# AD7799.net
KiCad netlist of a schematic drawn in Altium Designer
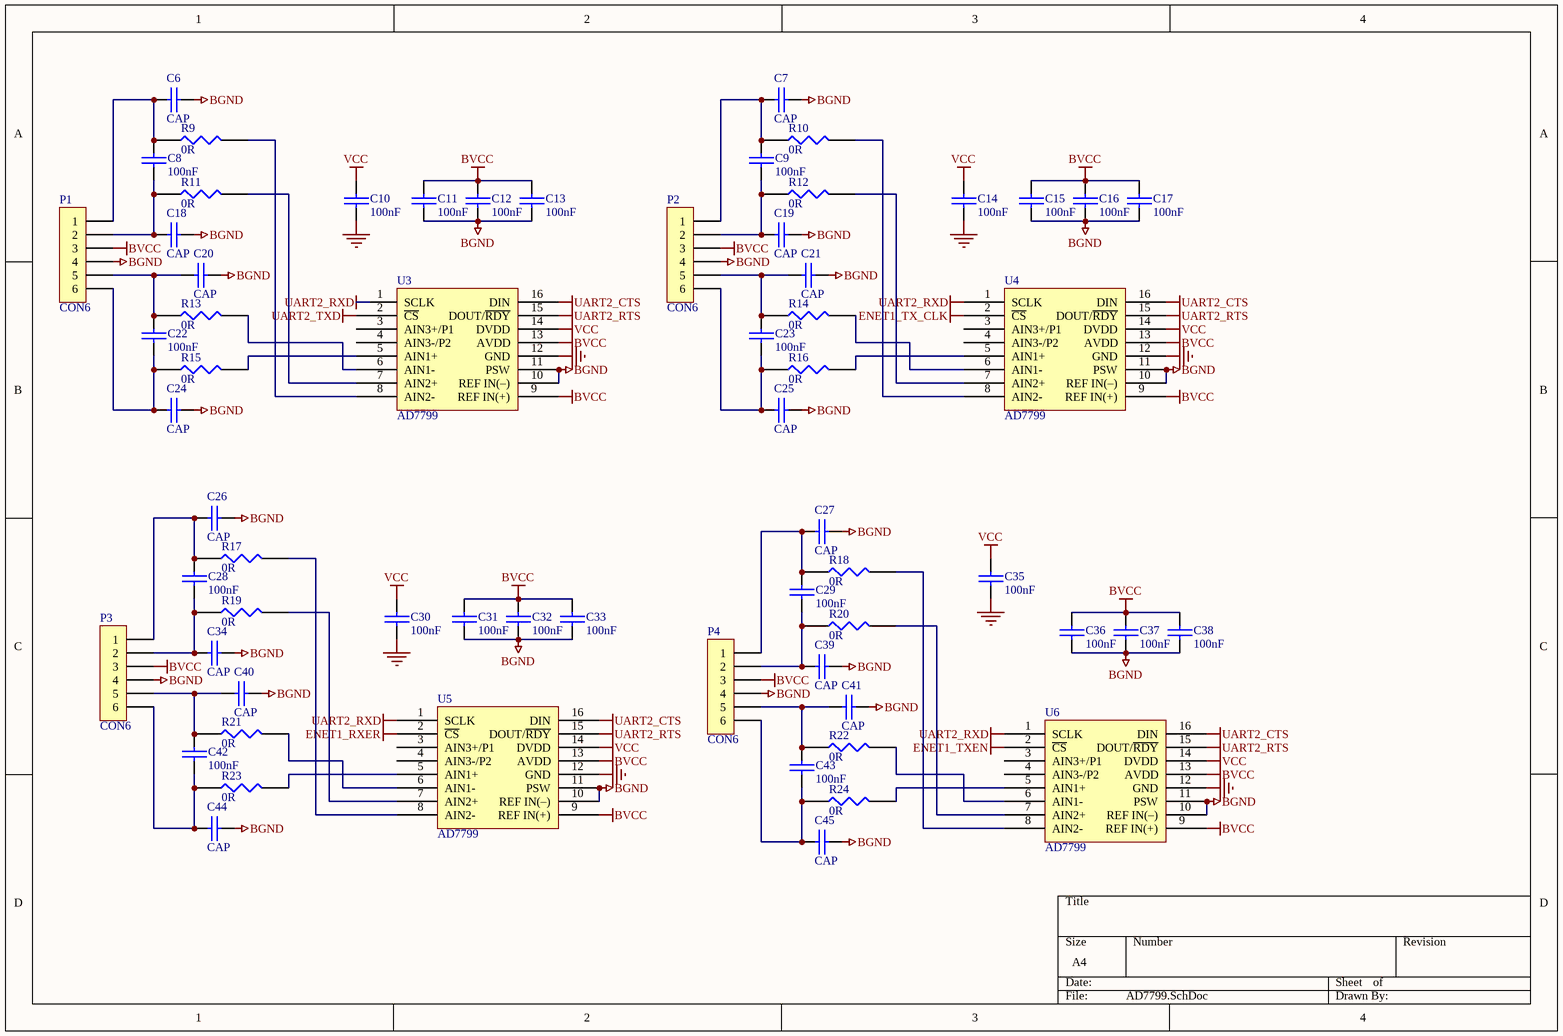
[diagram p0: AD7799.SchDoc]

(export (version "E")
  (design (tool "Eeschema 10.0.6"))
  (components
    (comp (ref "C6")
      (value "CAP")
      (footprint "0603_C")
      (description "Capacitor")
      (libsource (lib "*") (part "CAP"))
    )
    (comp (ref "C7")
      (value "CAP")
      (footprint "0603_C")
      (description "Capacitor")
      (libsource (lib "*") (part "CAP"))
    )
    (comp (ref "C8")
      (value "100nF")
      (footprint "0603_C")
      (description "Capacitor")
      (libsource (lib "*") (part "CAP"))
    )
    (comp (ref "C9")
      (value "100nF")
      (footprint "0603_C")
      (description "Capacitor")
      (libsource (lib "*") (part "CAP"))
    )
    (comp (ref "C10")
      (value "100nF")
      (footprint "0603_C")
      (description "Capacitor")
      (libsource (lib "*") (part "CAP"))
    )
    (comp (ref "C11")
      (value "100nF")
      (footprint "0603_C")
      (description "Capacitor")
      (libsource (lib "*") (part "CAP"))
    )
    (comp (ref "C12")
      (value "100nF")
      (footprint "0603_C")
      (description "Capacitor")
      (libsource (lib "*") (part "CAP"))
    )
    (comp (ref "C13")
      (value "100nF")
      (footprint "0603_C")
      (description "Capacitor")
      (libsource (lib "*") (part "CAP"))
    )
    (comp (ref "C14")
      (value "100nF")
      (footprint "0603_C")
      (description "Capacitor")
      (libsource (lib "*") (part "CAP"))
    )
    (comp (ref "C15")
      (value "100nF")
      (footprint "0603_C")
      (description "Capacitor")
      (libsource (lib "*") (part "CAP"))
    )
    (comp (ref "C16")
      (value "100nF")
      (footprint "0603_C")
      (description "Capacitor")
      (libsource (lib "*") (part "CAP"))
    )
    (comp (ref "C17")
      (value "100nF")
      (footprint "0603_C")
      (description "Capacitor")
      (libsource (lib "*") (part "CAP"))
    )
    (comp (ref "C18")
      (value "CAP")
      (footprint "0603_C")
      (description "Capacitor")
      (libsource (lib "*") (part "CAP"))
    )
    (comp (ref "C19")
      (value "CAP")
      (footprint "0603_C")
      (description "Capacitor")
      (libsource (lib "*") (part "CAP"))
    )
    (comp (ref "C20")
      (value "CAP")
      (footprint "0603_C")
      (description "Capacitor")
      (libsource (lib "*") (part "CAP"))
    )
    (comp (ref "C21")
      (value "CAP")
      (footprint "0603_C")
      (description "Capacitor")
      (libsource (lib "*") (part "CAP"))
    )
    (comp (ref "C22")
      (value "100nF")
      (footprint "0603_C")
      (description "Capacitor")
      (libsource (lib "*") (part "CAP"))
    )
    (comp (ref "C23")
      (value "100nF")
      (footprint "0603_C")
      (description "Capacitor")
      (libsource (lib "*") (part "CAP"))
    )
    (comp (ref "C24")
      (value "CAP")
      (footprint "0603_C")
      (description "Capacitor")
      (libsource (lib "*") (part "CAP"))
    )
    (comp (ref "C25")
      (value "CAP")
      (footprint "0603_C")
      (description "Capacitor")
      (libsource (lib "*") (part "CAP"))
    )
    (comp (ref "C26")
      (value "CAP")
      (footprint "0603_C")
      (description "Capacitor")
      (libsource (lib "*") (part "CAP"))
    )
    (comp (ref "C27")
      (value "CAP")
      (footprint "0603_C")
      (description "Capacitor")
      (libsource (lib "*") (part "CAP"))
    )
    (comp (ref "C28")
      (value "100nF")
      (footprint "0603_C")
      (description "Capacitor")
      (libsource (lib "*") (part "CAP"))
    )
    (comp (ref "C29")
      (value "100nF")
      (footprint "0603_C")
      (description "Capacitor")
      (libsource (lib "*") (part "CAP"))
    )
    (comp (ref "C30")
      (value "100nF")
      (footprint "0603_C")
      (description "Capacitor")
      (libsource (lib "*") (part "CAP"))
    )
    (comp (ref "C31")
      (value "100nF")
      (footprint "0603_C")
      (description "Capacitor")
      (libsource (lib "*") (part "CAP"))
    )
    (comp (ref "C32")
      (value "100nF")
      (footprint "0603_C")
      (description "Capacitor")
      (libsource (lib "*") (part "CAP"))
    )
    (comp (ref "C33")
      (value "100nF")
      (footprint "0603_C")
      (description "Capacitor")
      (libsource (lib "*") (part "CAP"))
    )
    (comp (ref "C34")
      (value "CAP")
      (footprint "0603_C")
      (description "Capacitor")
      (libsource (lib "*") (part "CAP"))
    )
    (comp (ref "C35")
      (value "100nF")
      (footprint "0603_C")
      (description "Capacitor")
      (libsource (lib "*") (part "CAP"))
    )
    (comp (ref "C36")
      (value "100nF")
      (footprint "0603_C")
      (description "Capacitor")
      (libsource (lib "*") (part "CAP"))
    )
    (comp (ref "C37")
      (value "100nF")
      (footprint "0603_C")
      (description "Capacitor")
      (libsource (lib "*") (part "CAP"))
    )
    (comp (ref "C38")
      (value "100nF")
      (footprint "0603_C")
      (description "Capacitor")
      (libsource (lib "*") (part "CAP"))
    )
    (comp (ref "C39")
      (value "CAP")
      (footprint "0603_C")
      (description "Capacitor")
      (libsource (lib "*") (part "CAP"))
    )
    (comp (ref "C40")
      (value "CAP")
      (footprint "0603_C")
      (description "Capacitor")
      (libsource (lib "*") (part "CAP"))
    )
    (comp (ref "C41")
      (value "CAP")
      (footprint "0603_C")
      (description "Capacitor")
      (libsource (lib "*") (part "CAP"))
    )
    (comp (ref "C42")
      (value "100nF")
      (footprint "0603_C")
      (description "Capacitor")
      (libsource (lib "*") (part "CAP"))
    )
    (comp (ref "C43")
      (value "100nF")
      (footprint "0603_C")
      (description "Capacitor")
      (libsource (lib "*") (part "CAP"))
    )
    (comp (ref "C44")
      (value "CAP")
      (footprint "0603_C")
      (description "Capacitor")
      (libsource (lib "*") (part "CAP"))
    )
    (comp (ref "C45")
      (value "CAP")
      (footprint "0603_C")
      (description "Capacitor")
      (libsource (lib "*") (part "CAP"))
    )
    (comp (ref "P1")
      (value "CON6")
      (footprint "DB142V-5.08-6P")
      (description "Connector")
      (libsource (lib "*") (part "CON6"))
    )
    (comp (ref "P2")
      (value "CON6")
      (footprint "DB142V-5.08-6P")
      (description "Connector")
      (libsource (lib "*") (part "CON6"))
    )
    (comp (ref "P3")
      (value "CON6")
      (footprint "DB142V-5.08-6P")
      (description "Connector")
      (libsource (lib "*") (part "CON6"))
    )
    (comp (ref "P4")
      (value "CON6")
      (footprint "DB142V-5.08-6P")
      (description "Connector")
      (libsource (lib "*") (part "CON6"))
    )
    (comp (ref "R9") (value "0R") (footprint "0603_R") (libsource (lib "*") (part "RES1")))
    (comp (ref "R10") (value "0R") (footprint "0603_R") (libsource (lib "*") (part "RES1")))
    (comp (ref "R11") (value "0R") (footprint "0603_R") (libsource (lib "*") (part "RES1")))
    (comp (ref "R12") (value "0R") (footprint "0603_R") (libsource (lib "*") (part "RES1")))
    (comp (ref "R13") (value "0R") (footprint "0603_R") (libsource (lib "*") (part "RES1")))
    (comp (ref "R14") (value "0R") (footprint "0603_R") (libsource (lib "*") (part "RES1")))
    (comp (ref "R15") (value "0R") (footprint "0603_R") (libsource (lib "*") (part "RES1")))
    (comp (ref "R16") (value "0R") (footprint "0603_R") (libsource (lib "*") (part "RES1")))
    (comp (ref "R17") (value "0R") (footprint "0603_R") (libsource (lib "*") (part "RES1")))
    (comp (ref "R18") (value "0R") (footprint "0603_R") (libsource (lib "*") (part "RES1")))
    (comp (ref "R19") (value "0R") (footprint "0603_R") (libsource (lib "*") (part "RES1")))
    (comp (ref "R20") (value "0R") (footprint "0603_R") (libsource (lib "*") (part "RES1")))
    (comp (ref "R21") (value "0R") (footprint "0603_R") (libsource (lib "*") (part "RES1")))
    (comp (ref "R22") (value "0R") (footprint "0603_R") (libsource (lib "*") (part "RES1")))
    (comp (ref "R23") (value "0R") (footprint "0603_R") (libsource (lib "*") (part "RES1")))
    (comp (ref "R24") (value "0R") (footprint "0603_R") (libsource (lib "*") (part "RES1")))
    (comp (ref "U3") (value "AD7799") (footprint "TSSOP16") (libsource (lib "*") (part "AD7799")))
    (comp (ref "U4") (value "AD7799") (footprint "TSSOP16") (libsource (lib "*") (part "AD7799")))
    (comp (ref "U5") (value "AD7799") (footprint "TSSOP16") (libsource (lib "*") (part "AD7799")))
    (comp (ref "U6") (value "AD7799") (footprint "TSSOP16") (libsource (lib "*") (part "AD7799")))
  )
  (nets
    (net (code "1") (name "BGND") (class "Default")
      (node (ref "C11") (pin "2") (pinfunction "2_2") (pintype "passive"))
      (node (ref "C12") (pin "2") (pinfunction "2_2") (pintype "passive"))
      (node (ref "C13") (pin "2") (pinfunction "2_2") (pintype "passive"))
      (node (ref "C15") (pin "2") (pinfunction "2_2") (pintype "passive"))
      (node (ref "C16") (pin "2") (pinfunction "2_2") (pintype "passive"))
      (node (ref "C17") (pin "2") (pinfunction "2_2") (pintype "passive"))
      (node (ref "C18") (pin "2") (pinfunction "2_2") (pintype "passive"))
      (node (ref "C19") (pin "2") (pinfunction "2_2") (pintype "passive"))
      (node (ref "C20") (pin "2") (pinfunction "2_2") (pintype "passive"))
      (node (ref "C21") (pin "2") (pinfunction "2_2") (pintype "passive"))
      (node (ref "C24") (pin "2") (pinfunction "2_2") (pintype "passive"))
      (node (ref "C25") (pin "2") (pinfunction "2_2") (pintype "passive"))
      (node (ref "C26") (pin "2") (pinfunction "2_2") (pintype "passive"))
      (node (ref "C27") (pin "2") (pinfunction "2_2") (pintype "passive"))
      (node (ref "C31") (pin "2") (pinfunction "2_2") (pintype "passive"))
      (node (ref "C32") (pin "2") (pinfunction "2_2") (pintype "passive"))
      (node (ref "C33") (pin "2") (pinfunction "2_2") (pintype "passive"))
      (node (ref "C34") (pin "2") (pinfunction "2_2") (pintype "passive"))
      (node (ref "C36") (pin "2") (pinfunction "2_2") (pintype "passive"))
      (node (ref "C37") (pin "2") (pinfunction "2_2") (pintype "passive"))
      (node (ref "C38") (pin "2") (pinfunction "2_2") (pintype "passive"))
      (node (ref "C39") (pin "2") (pinfunction "2_2") (pintype "passive"))
      (node (ref "C40") (pin "2") (pinfunction "2_2") (pintype "passive"))
      (node (ref "C41") (pin "2") (pinfunction "2_2") (pintype "passive"))
      (node (ref "C44") (pin "2") (pinfunction "2_2") (pintype "passive"))
      (node (ref "C45") (pin "2") (pinfunction "2_2") (pintype "passive"))
      (node (ref "C6") (pin "2") (pinfunction "2_2") (pintype "passive"))
      (node (ref "C7") (pin "2") (pinfunction "2_2") (pintype "passive"))
      (node (ref "P1") (pin "4") (pinfunction "4_4") (pintype "passive"))
      (node (ref "P2") (pin "4") (pinfunction "4_4") (pintype "passive"))
      (node (ref "P3") (pin "4") (pinfunction "4_4") (pintype "passive"))
      (node (ref "P4") (pin "4") (pinfunction "4_4") (pintype "passive"))
      (node (ref "U3") (pin "10") (pinfunction "REF_IN(–)_10") (pintype "passive"))
      (node (ref "U3") (pin "11") (pinfunction "PSW_11") (pintype "passive"))
      (node (ref "U4") (pin "10") (pinfunction "REF_IN(–)_10") (pintype "passive"))
      (node (ref "U4") (pin "11") (pinfunction "PSW_11") (pintype "passive"))
      (node (ref "U5") (pin "10") (pinfunction "REF_IN(–)_10") (pintype "passive"))
      (node (ref "U5") (pin "11") (pinfunction "PSW_11") (pintype "passive"))
      (node (ref "U6") (pin "10") (pinfunction "REF_IN(–)_10") (pintype "passive"))
      (node (ref "U6") (pin "11") (pinfunction "PSW_11") (pintype "passive"))
    )
    (net (code "2") (name "BVCC") (class "Default")
      (node (ref "C11") (pin "1") (pinfunction "1_1") (pintype "passive"))
      (node (ref "C12") (pin "1") (pinfunction "1_1") (pintype "passive"))
      (node (ref "C13") (pin "1") (pinfunction "1_1") (pintype "passive"))
      (node (ref "C15") (pin "1") (pinfunction "1_1") (pintype "passive"))
      (node (ref "C16") (pin "1") (pinfunction "1_1") (pintype "passive"))
      (node (ref "C17") (pin "1") (pinfunction "1_1") (pintype "passive"))
      (node (ref "C31") (pin "1") (pinfunction "1_1") (pintype "passive"))
      (node (ref "C32") (pin "1") (pinfunction "1_1") (pintype "passive"))
      (node (ref "C33") (pin "1") (pinfunction "1_1") (pintype "passive"))
      (node (ref "C36") (pin "1") (pinfunction "1_1") (pintype "passive"))
      (node (ref "C37") (pin "1") (pinfunction "1_1") (pintype "passive"))
      (node (ref "C38") (pin "1") (pinfunction "1_1") (pintype "passive"))
      (node (ref "P1") (pin "3") (pinfunction "3_3") (pintype "passive"))
      (node (ref "P2") (pin "3") (pinfunction "3_3") (pintype "passive"))
      (node (ref "P3") (pin "3") (pinfunction "3_3") (pintype "passive"))
      (node (ref "P4") (pin "3") (pinfunction "3_3") (pintype "passive"))
      (node (ref "U3") (pin "13") (pinfunction "AVDD_13") (pintype "passive"))
      (node (ref "U3") (pin "9") (pinfunction "REF_IN(+)_9") (pintype "passive"))
      (node (ref "U4") (pin "13") (pinfunction "AVDD_13") (pintype "passive"))
      (node (ref "U4") (pin "9") (pinfunction "REF_IN(+)_9") (pintype "passive"))
      (node (ref "U5") (pin "13") (pinfunction "AVDD_13") (pintype "passive"))
      (node (ref "U5") (pin "9") (pinfunction "REF_IN(+)_9") (pintype "passive"))
      (node (ref "U6") (pin "13") (pinfunction "AVDD_13") (pintype "passive"))
      (node (ref "U6") (pin "9") (pinfunction "REF_IN(+)_9") (pintype "passive"))
    )
    (net (code "3") (name "ENET1_RXER") (class "Default")
      (node (ref "U5") (pin "2") (pinfunction "~{CS}_2") (pintype "passive"))
    )
    (net (code "4") (name "ENET1_TXEN") (class "Default")
      (node (ref "U6") (pin "2") (pinfunction "~{CS}_2") (pintype "passive"))
    )
    (net (code "5") (name "ENET1_TX_CLK") (class "Default")
      (node (ref "U4") (pin "2") (pinfunction "~{CS}_2") (pintype "passive"))
    )
    (net (code "6") (name "GND") (class "Default")
      (node (ref "C10") (pin "2") (pinfunction "2_2") (pintype "passive"))
      (node (ref "C14") (pin "2") (pinfunction "2_2") (pintype "passive"))
      (node (ref "C30") (pin "2") (pinfunction "2_2") (pintype "passive"))
      (node (ref "C35") (pin "2") (pinfunction "2_2") (pintype "passive"))
      (node (ref "U3") (pin "12") (pinfunction "GND_12") (pintype "passive"))
      (node (ref "U4") (pin "12") (pinfunction "GND_12") (pintype "passive"))
      (node (ref "U5") (pin "12") (pinfunction "GND_12") (pintype "passive"))
      (node (ref "U6") (pin "12") (pinfunction "GND_12") (pintype "passive"))
    )
    (net (code "7") (name "Net-(C6-Pad1)") (class "Default")
      (node (ref "C6") (pin "1") (pinfunction "1_1") (pintype "passive"))
      (node (ref "C8") (pin "1") (pinfunction "1_1") (pintype "passive"))
      (node (ref "P1") (pin "1") (pinfunction "1_1") (pintype "passive"))
      (node (ref "R9") (pin "1") (pinfunction "1_1") (pintype "passive"))
    )
    (net (code "8") (name "Net-(C7-Pad1)") (class "Default")
      (node (ref "C7") (pin "1") (pinfunction "1_1") (pintype "passive"))
      (node (ref "C9") (pin "1") (pinfunction "1_1") (pintype "passive"))
      (node (ref "P2") (pin "1") (pinfunction "1_1") (pintype "passive"))
      (node (ref "R10") (pin "1") (pinfunction "1_1") (pintype "passive"))
    )
    (net (code "9") (name "Net-(C18-Pad1)") (class "Default")
      (node (ref "C18") (pin "1") (pinfunction "1_1") (pintype "passive"))
      (node (ref "C8") (pin "2") (pinfunction "2_2") (pintype "passive"))
      (node (ref "P1") (pin "2") (pinfunction "2_2") (pintype "passive"))
      (node (ref "R11") (pin "1") (pinfunction "1_1") (pintype "passive"))
    )
    (net (code "10") (name "Net-(C19-Pad1)") (class "Default")
      (node (ref "C19") (pin "1") (pinfunction "1_1") (pintype "passive"))
      (node (ref "C9") (pin "2") (pinfunction "2_2") (pintype "passive"))
      (node (ref "P2") (pin "2") (pinfunction "2_2") (pintype "passive"))
      (node (ref "R12") (pin "1") (pinfunction "1_1") (pintype "passive"))
    )
    (net (code "11") (name "Net-(C20-Pad1)") (class "Default")
      (node (ref "C20") (pin "1") (pinfunction "1_1") (pintype "passive"))
      (node (ref "C22") (pin "1") (pinfunction "1_1") (pintype "passive"))
      (node (ref "P1") (pin "5") (pinfunction "5_5") (pintype "passive"))
      (node (ref "R13") (pin "1") (pinfunction "1_1") (pintype "passive"))
    )
    (net (code "12") (name "Net-(C21-Pad1)") (class "Default")
      (node (ref "C21") (pin "1") (pinfunction "1_1") (pintype "passive"))
      (node (ref "C23") (pin "1") (pinfunction "1_1") (pintype "passive"))
      (node (ref "P2") (pin "5") (pinfunction "5_5") (pintype "passive"))
      (node (ref "R14") (pin "1") (pinfunction "1_1") (pintype "passive"))
    )
    (net (code "13") (name "Net-(C22-Pad2)") (class "Default")
      (node (ref "C22") (pin "2") (pinfunction "2_2") (pintype "passive"))
      (node (ref "C24") (pin "1") (pinfunction "1_1") (pintype "passive"))
      (node (ref "P1") (pin "6") (pinfunction "6_6") (pintype "passive"))
      (node (ref "R15") (pin "1") (pinfunction "1_1") (pintype "passive"))
    )
    (net (code "14") (name "Net-(C23-Pad2)") (class "Default")
      (node (ref "C23") (pin "2") (pinfunction "2_2") (pintype "passive"))
      (node (ref "C25") (pin "1") (pinfunction "1_1") (pintype "passive"))
      (node (ref "P2") (pin "6") (pinfunction "6_6") (pintype "passive"))
      (node (ref "R16") (pin "1") (pinfunction "1_1") (pintype "passive"))
    )
    (net (code "15") (name "Net-(C26-Pad1)") (class "Default")
      (node (ref "C26") (pin "1") (pinfunction "1_1") (pintype "passive"))
      (node (ref "C28") (pin "1") (pinfunction "1_1") (pintype "passive"))
      (node (ref "P3") (pin "1") (pinfunction "1_1") (pintype "passive"))
      (node (ref "R17") (pin "1") (pinfunction "1_1") (pintype "passive"))
    )
    (net (code "16") (name "Net-(C27-Pad1)") (class "Default")
      (node (ref "C27") (pin "1") (pinfunction "1_1") (pintype "passive"))
      (node (ref "C29") (pin "1") (pinfunction "1_1") (pintype "passive"))
      (node (ref "P4") (pin "1") (pinfunction "1_1") (pintype "passive"))
      (node (ref "R18") (pin "1") (pinfunction "1_1") (pintype "passive"))
    )
    (net (code "17") (name "Net-(C28-Pad2)") (class "Default")
      (node (ref "C28") (pin "2") (pinfunction "2_2") (pintype "passive"))
      (node (ref "C34") (pin "1") (pinfunction "1_1") (pintype "passive"))
      (node (ref "P3") (pin "2") (pinfunction "2_2") (pintype "passive"))
      (node (ref "R19") (pin "1") (pinfunction "1_1") (pintype "passive"))
    )
    (net (code "18") (name "Net-(C29-Pad2)") (class "Default")
      (node (ref "C29") (pin "2") (pinfunction "2_2") (pintype "passive"))
      (node (ref "C39") (pin "1") (pinfunction "1_1") (pintype "passive"))
      (node (ref "P4") (pin "2") (pinfunction "2_2") (pintype "passive"))
      (node (ref "R20") (pin "1") (pinfunction "1_1") (pintype "passive"))
    )
    (net (code "19") (name "Net-(C40-Pad1)") (class "Default")
      (node (ref "C40") (pin "1") (pinfunction "1_1") (pintype "passive"))
      (node (ref "C42") (pin "1") (pinfunction "1_1") (pintype "passive"))
      (node (ref "P3") (pin "5") (pinfunction "5_5") (pintype "passive"))
      (node (ref "R21") (pin "1") (pinfunction "1_1") (pintype "passive"))
    )
    (net (code "20") (name "Net-(C41-Pad1)") (class "Default")
      (node (ref "C41") (pin "1") (pinfunction "1_1") (pintype "passive"))
      (node (ref "C43") (pin "1") (pinfunction "1_1") (pintype "passive"))
      (node (ref "P4") (pin "5") (pinfunction "5_5") (pintype "passive"))
      (node (ref "R22") (pin "1") (pinfunction "1_1") (pintype "passive"))
    )
    (net (code "21") (name "Net-(C42-Pad2)") (class "Default")
      (node (ref "C42") (pin "2") (pinfunction "2_2") (pintype "passive"))
      (node (ref "C44") (pin "1") (pinfunction "1_1") (pintype "passive"))
      (node (ref "P3") (pin "6") (pinfunction "6_6") (pintype "passive"))
      (node (ref "R23") (pin "1") (pinfunction "1_1") (pintype "passive"))
    )
    (net (code "22") (name "Net-(C43-Pad2)") (class "Default")
      (node (ref "C43") (pin "2") (pinfunction "2_2") (pintype "passive"))
      (node (ref "C45") (pin "1") (pinfunction "1_1") (pintype "passive"))
      (node (ref "P4") (pin "6") (pinfunction "6_6") (pintype "passive"))
      (node (ref "R24") (pin "1") (pinfunction "1_1") (pintype "passive"))
    )
    (net (code "23") (name "Net-(U3-AIN1+)") (class "Default")
      (node (ref "R15") (pin "2") (pinfunction "2_2") (pintype "passive"))
      (node (ref "U3") (pin "5") (pinfunction "AIN1+_5") (pintype "passive"))
    )
    (net (code "24") (name "Net-(U3-AIN1-)") (class "Default")
      (node (ref "R13") (pin "2") (pinfunction "2_2") (pintype "passive"))
      (node (ref "U3") (pin "6") (pinfunction "AIN1-_6") (pintype "passive"))
    )
    (net (code "25") (name "Net-(U3-AIN2+)") (class "Default")
      (node (ref "R11") (pin "2") (pinfunction "2_2") (pintype "passive"))
      (node (ref "U3") (pin "7") (pinfunction "AIN2+_7") (pintype "passive"))
    )
    (net (code "26") (name "Net-(U3-AIN2-)") (class "Default")
      (node (ref "R9") (pin "2") (pinfunction "2_2") (pintype "passive"))
      (node (ref "U3") (pin "8") (pinfunction "AIN2-_8") (pintype "passive"))
    )
    (net (code "27") (name "Net-(U4-AIN1+)") (class "Default")
      (node (ref "R16") (pin "2") (pinfunction "2_2") (pintype "passive"))
      (node (ref "U4") (pin "5") (pinfunction "AIN1+_5") (pintype "passive"))
    )
    (net (code "28") (name "Net-(U4-AIN1-)") (class "Default")
      (node (ref "R14") (pin "2") (pinfunction "2_2") (pintype "passive"))
      (node (ref "U4") (pin "6") (pinfunction "AIN1-_6") (pintype "passive"))
    )
    (net (code "29") (name "Net-(U4-AIN2+)") (class "Default")
      (node (ref "R12") (pin "2") (pinfunction "2_2") (pintype "passive"))
      (node (ref "U4") (pin "7") (pinfunction "AIN2+_7") (pintype "passive"))
    )
    (net (code "30") (name "Net-(U4-AIN2-)") (class "Default")
      (node (ref "R10") (pin "2") (pinfunction "2_2") (pintype "passive"))
      (node (ref "U4") (pin "8") (pinfunction "AIN2-_8") (pintype "passive"))
    )
    (net (code "31") (name "Net-(U5-AIN1+)") (class "Default")
      (node (ref "R23") (pin "2") (pinfunction "2_2") (pintype "passive"))
      (node (ref "U5") (pin "5") (pinfunction "AIN1+_5") (pintype "passive"))
    )
    (net (code "32") (name "Net-(U5-AIN1-)") (class "Default")
      (node (ref "R21") (pin "2") (pinfunction "2_2") (pintype "passive"))
      (node (ref "U5") (pin "6") (pinfunction "AIN1-_6") (pintype "passive"))
    )
    (net (code "33") (name "Net-(U5-AIN2+)") (class "Default")
      (node (ref "R19") (pin "2") (pinfunction "2_2") (pintype "passive"))
      (node (ref "U5") (pin "7") (pinfunction "AIN2+_7") (pintype "passive"))
    )
    (net (code "34") (name "Net-(U5-AIN2-)") (class "Default")
      (node (ref "R17") (pin "2") (pinfunction "2_2") (pintype "passive"))
      (node (ref "U5") (pin "8") (pinfunction "AIN2-_8") (pintype "passive"))
    )
    (net (code "35") (name "Net-(U6-AIN1+)") (class "Default")
      (node (ref "R24") (pin "2") (pinfunction "2_2") (pintype "passive"))
      (node (ref "U6") (pin "5") (pinfunction "AIN1+_5") (pintype "passive"))
    )
    (net (code "36") (name "Net-(U6-AIN1-)") (class "Default")
      (node (ref "R22") (pin "2") (pinfunction "2_2") (pintype "passive"))
      (node (ref "U6") (pin "6") (pinfunction "AIN1-_6") (pintype "passive"))
    )
    (net (code "37") (name "Net-(U6-AIN2+)") (class "Default")
      (node (ref "R20") (pin "2") (pinfunction "2_2") (pintype "passive"))
      (node (ref "U6") (pin "7") (pinfunction "AIN2+_7") (pintype "passive"))
    )
    (net (code "38") (name "Net-(U6-AIN2-)") (class "Default")
      (node (ref "R18") (pin "2") (pinfunction "2_2") (pintype "passive"))
      (node (ref "U6") (pin "8") (pinfunction "AIN2-_8") (pintype "passive"))
    )
    (net (code "39") (name "UART2_CTS") (class "Default")
      (node (ref "U3") (pin "16") (pinfunction "DIN_16") (pintype "passive"))
      (node (ref "U4") (pin "16") (pinfunction "DIN_16") (pintype "passive"))
      (node (ref "U5") (pin "16") (pinfunction "DIN_16") (pintype "passive"))
      (node (ref "U6") (pin "16") (pinfunction "DIN_16") (pintype "passive"))
    )
    (net (code "40") (name "UART2_RTS") (class "Default")
      (node (ref "U3") (pin "15") (pinfunction "DOUT/~{RDY}_15") (pintype "passive"))
      (node (ref "U4") (pin "15") (pinfunction "DOUT/~{RDY}_15") (pintype "passive"))
      (node (ref "U5") (pin "15") (pinfunction "DOUT/~{RDY}_15") (pintype "passive"))
      (node (ref "U6") (pin "15") (pinfunction "DOUT/~{RDY}_15") (pintype "passive"))
    )
    (net (code "41") (name "UART2_RXD") (class "Default")
      (node (ref "U3") (pin "1") (pinfunction "SCLK_1") (pintype "passive"))
      (node (ref "U4") (pin "1") (pinfunction "SCLK_1") (pintype "passive"))
      (node (ref "U5") (pin "1") (pinfunction "SCLK_1") (pintype "passive"))
      (node (ref "U6") (pin "1") (pinfunction "SCLK_1") (pintype "passive"))
    )
    (net (code "42") (name "UART2_TXD") (class "Default")
      (node (ref "U3") (pin "2") (pinfunction "~{CS}_2") (pintype "passive"))
    )
    (net (code "43") (name "VCC") (class "Default")
      (node (ref "C10") (pin "1") (pinfunction "1_1") (pintype "passive"))
      (node (ref "C14") (pin "1") (pinfunction "1_1") (pintype "passive"))
      (node (ref "C30") (pin "1") (pinfunction "1_1") (pintype "passive"))
      (node (ref "C35") (pin "1") (pinfunction "1_1") (pintype "passive"))
      (node (ref "U3") (pin "14") (pinfunction "DVDD_14") (pintype "passive"))
      (node (ref "U4") (pin "14") (pinfunction "DVDD_14") (pintype "passive"))
      (node (ref "U5") (pin "14") (pinfunction "DVDD_14") (pintype "passive"))
      (node (ref "U6") (pin "14") (pinfunction "DVDD_14") (pintype "passive"))
    )
    (net (code "44") (name "unconnected-(U3-AIN3+{slash}P1-Pad3)") (class "Default")
      (node (ref "U3") (pin "3") (pinfunction "AIN3+/P1_3") (pintype "passive"))
    )
    (net (code "45") (name "unconnected-(U3-AIN3-{slash}P2-Pad4)") (class "Default")
      (node (ref "U3") (pin "4") (pinfunction "AIN3-/P2_4") (pintype "passive"))
    )
    (net (code "46") (name "unconnected-(U4-AIN3+{slash}P1-Pad3)") (class "Default")
      (node (ref "U4") (pin "3") (pinfunction "AIN3+/P1_3") (pintype "passive"))
    )
    (net (code "47") (name "unconnected-(U4-AIN3-{slash}P2-Pad4)") (class "Default")
      (node (ref "U4") (pin "4") (pinfunction "AIN3-/P2_4") (pintype "passive"))
    )
    (net (code "48") (name "unconnected-(U5-AIN3+{slash}P1-Pad3)") (class "Default")
      (node (ref "U5") (pin "3") (pinfunction "AIN3+/P1_3") (pintype "passive"))
    )
    (net (code "49") (name "unconnected-(U5-AIN3-{slash}P2-Pad4)") (class "Default")
      (node (ref "U5") (pin "4") (pinfunction "AIN3-/P2_4") (pintype "passive"))
    )
    (net (code "50") (name "unconnected-(U6-AIN3+{slash}P1-Pad3)") (class "Default")
      (node (ref "U6") (pin "3") (pinfunction "AIN3+/P1_3") (pintype "passive"))
    )
    (net (code "51") (name "unconnected-(U6-AIN3-{slash}P2-Pad4)") (class "Default")
      (node (ref "U6") (pin "4") (pinfunction "AIN3-/P2_4") (pintype "passive"))
    )
  )
)
